# DriverAndProtection.net
KiCad netlist of a schematic drawn in Altium Designer
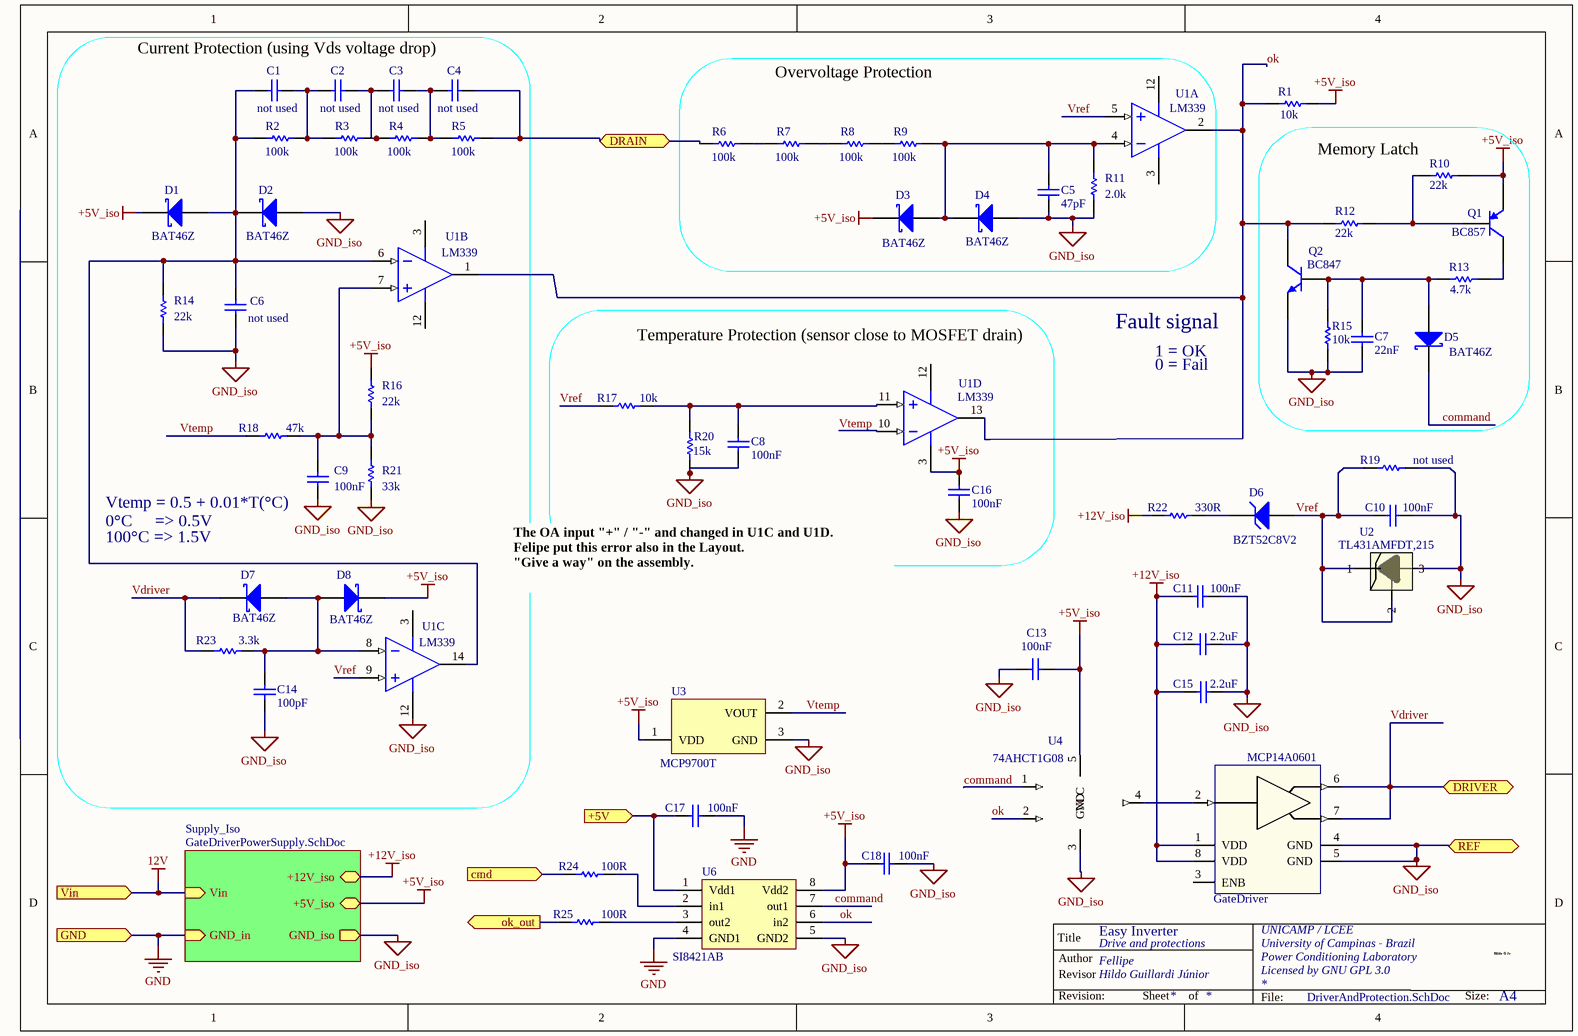
[diagram p0: DriverAndProtection.SchDoc]

(export (version "E")
  (design (tool "Eeschema 10.0.6"))
  (components
    (comp (ref "C1")
      (value "not used")
      (footprint "0805_W")
      (description "Capacitor")
      (fields (field (name "PUBLISHER") "Altium Limited"))
      (libsource (lib "Inversor_LCEE") (part "Cap_0805"))
    )
    (comp (ref "C2")
      (value "not used")
      (footprint "0805_W")
      (description "Capacitor")
      (fields (field (name "PUBLISHER") "Altium Limited"))
      (libsource (lib "Inversor_LCEE") (part "Cap_0805"))
    )
    (comp (ref "C3")
      (value "not used")
      (footprint "0805_W")
      (description "Capacitor")
      (fields (field (name "PUBLISHER") "Altium Limited"))
      (libsource (lib "Inversor_LCEE") (part "Cap_0805"))
    )
    (comp (ref "C4")
      (value "not used")
      (footprint "0805_W")
      (description "Capacitor")
      (fields (field (name "PUBLISHER") "Altium Limited"))
      (libsource (lib "Inversor_LCEE") (part "Cap_0805"))
    )
    (comp (ref "C5")
      (value "47pF")
      (footprint "0805_W")
      (description "Capacitor")
      (libsource (lib "Inversor_LCEE") (part "Cap_0805"))
    )
    (comp (ref "C6")
      (value "not used")
      (footprint "0805_W")
      (description "Capacitor")
      (libsource (lib "Inversor_LCEE") (part "Cap_0805"))
    )
    (comp (ref "C7")
      (value "22nF")
      (footprint "0805_W")
      (description "Capacitor")
      (libsource (lib "Inversor_LCEE") (part "Cap_0805"))
    )
    (comp (ref "C8")
      (value "100nF")
      (footprint "0805_W")
      (description "Capacitor")
      (libsource (lib "Inversor_LCEE") (part "Cap_0805"))
    )
    (comp (ref "C9")
      (value "100nF")
      (footprint "0805_W")
      (description "Capacitor")
      (libsource (lib "Inversor_LCEE") (part "Cap_0805"))
    )
    (comp (ref "C10")
      (value "100nF")
      (footprint "0805_W")
      (description "Capacitor")
      (libsource (lib "Inversor_LCEE") (part "Cap_0805"))
    )
    (comp (ref "C11")
      (value "100nF")
      (footprint "0805_W")
      (description "Capacitor")
      (libsource (lib "Inversor_LCEE") (part "Cap_0805"))
    )
    (comp (ref "C12")
      (value "2.2uF")
      (footprint "0805_W")
      (description "Capacitor nao polarizado")
      (libsource (lib "Sch_LCEE") (part "Capacitor_nao_polarizado"))
    )
    (comp (ref "C13")
      (value "100nF")
      (footprint "0805_W")
      (description "Capacitor")
      (libsource (lib "Inversor_LCEE") (part "Cap_0805"))
    )
    (comp (ref "C14")
      (value "100pF")
      (footprint "0805_W")
      (description "Capacitor")
      (libsource (lib "Inversor_LCEE") (part "Cap_0805"))
    )
    (comp (ref "C15")
      (value "2.2uF")
      (footprint "0805_W")
      (description "Capacitor nao polarizado")
      (libsource (lib "Sch_LCEE") (part "Capacitor_nao_polarizado"))
    )
    (comp (ref "C16")
      (value "100nF")
      (footprint "0805_W")
      (description "Capacitor")
      (libsource (lib "Inversor_LCEE") (part "Cap_0805"))
    )
    (comp (ref "C17")
      (value "100nF")
      (footprint "0805_W")
      (description "Capacitor")
      (libsource (lib "Inversor_LCEE") (part "Cap_0805"))
    )
    (comp (ref "C18")
      (value "100nF")
      (footprint "0805_W")
      (description "Capacitor")
      (libsource (lib "Inversor_LCEE") (part "Cap_0805"))
    )
    (comp (ref "D1")
      (value "BAT46Z")
      (footprint "pcb_lcee:SOD-123")
      (description "Schottky Diode")
      (libsource (lib "Miscellaneous Devices") (part "D Schottky"))
    )
    (comp (ref "D2")
      (value "BAT46Z")
      (footprint "pcb_lcee:SOD-123")
      (description "Schottky Diode")
      (libsource (lib "Miscellaneous Devices") (part "D Schottky"))
    )
    (comp (ref "D3")
      (value "BAT46Z")
      (footprint "pcb_lcee:SOD-123")
      (description "Schottky Diode")
      (libsource (lib "Miscellaneous Devices") (part "D Schottky"))
    )
    (comp (ref "D4")
      (value "BAT46Z")
      (footprint "pcb_lcee:SOD-123")
      (description "Schottky Diode")
      (libsource (lib "Miscellaneous Devices") (part "D Schottky"))
    )
    (comp (ref "D5")
      (value "BAT46Z")
      (footprint "SOD-123")
      (description "Diodo Schottky")
      (libsource (lib "Sch_LCEE") (part "Schottky"))
    )
    (comp (ref "D6")
      (value "BZT52C8V2")
      (footprint "SOD-123")
      (description "Zener Diode")
      (libsource (lib "Miscellaneous Devices") (part "D Zener"))
    )
    (comp (ref "D7")
      (value "BAT46Z")
      (footprint "pcb_lcee:SOD-123")
      (description "Schottky Diode")
      (libsource (lib "Miscellaneous Devices") (part "D Schottky"))
    )
    (comp (ref "D8")
      (value "BAT46Z")
      (footprint "pcb_lcee:SOD-123")
      (description "Schottky Diode")
      (libsource (lib "Miscellaneous Devices") (part "D Schottky"))
    )
    (comp (ref "GateDriver")
      (value "MCP14A0601")
      (footprint "SOIC-8N")
      (libsource (lib "Inverter_LCEE") (part "GateDriver"))
    )
    (comp (ref "Q1")
      (value "BC857")
      (footprint "SOT-23-TT3_N")
      (description "PNP General-purpose Transistor")
      (libsource (lib "Philips Discrete BJT - Low Power") (part "BC857"))
    )
    (comp (ref "Q2")
      (value "BC847")
      (footprint "SOT-23-TT3_N")
      (description "NPN General-purpose Transistor")
      (libsource (lib "Philips Discrete BJT - Low Power") (part "BC847"))
    )
    (comp (ref "R1")
      (value "10k")
      (footprint "0805_W")
      (description "Resistor")
      (libsource (lib "Inversor_LCEE") (part "Res_0805"))
    )
    (comp (ref "R2")
      (value "100k")
      (footprint "0805_W")
      (description "Resistor")
      (libsource (lib "Inversor_LCEE") (part "Res_0805"))
    )
    (comp (ref "R3")
      (value "100k")
      (footprint "0805_W")
      (description "Resistor")
      (libsource (lib "Inversor_LCEE") (part "Res_0805"))
    )
    (comp (ref "R4")
      (value "100k")
      (footprint "0805_W")
      (description "Resistor")
      (libsource (lib "Inversor_LCEE") (part "Res_0805"))
    )
    (comp (ref "R5")
      (value "100k")
      (footprint "0805_W")
      (description "Resistor")
      (libsource (lib "Inversor_LCEE") (part "Res_0805"))
    )
    (comp (ref "R6")
      (value "100k")
      (footprint "0805_W")
      (description "Resistor")
      (libsource (lib "Inversor_LCEE") (part "Res_0805"))
    )
    (comp (ref "R7")
      (value "100k")
      (footprint "0805_W")
      (description "Resistor")
      (libsource (lib "Inversor_LCEE") (part "Res_0805"))
    )
    (comp (ref "R8")
      (value "100k")
      (footprint "0805_W")
      (description "Resistor")
      (libsource (lib "Inversor_LCEE") (part "Res_0805"))
    )
    (comp (ref "R9")
      (value "100k")
      (footprint "0805_W")
      (description "Resistor")
      (libsource (lib "Inversor_LCEE") (part "Res_0805"))
    )
    (comp (ref "R10")
      (value "22k")
      (footprint "0805_W")
      (description "Resistor- Not Used")
      (libsource (lib "Inversor_LCEE") (part "Res_0805"))
    )
    (comp (ref "R11")
      (value "2.0k")
      (footprint "0805_W")
      (description "Resistor")
      (libsource (lib "Inversor_LCEE") (part "Res_0805"))
    )
    (comp (ref "R12")
      (value "22k")
      (footprint "0805_W")
      (description "Resistor")
      (libsource (lib "Inversor_LCEE") (part "Res_0805"))
    )
    (comp (ref "R13")
      (value "4.7k")
      (footprint "0805_W")
      (description "Resistor")
      (libsource (lib "Inversor_LCEE") (part "Res_0805"))
    )
    (comp (ref "R14")
      (value "22k")
      (footprint "0805_W")
      (description "Resistor")
      (libsource (lib "Inversor_LCEE") (part "Res_0805"))
    )
    (comp (ref "R15")
      (value "10k")
      (footprint "0805_W")
      (description "Resistor- Not Used")
      (libsource (lib "Inversor_LCEE") (part "Res_0805"))
    )
    (comp (ref "R16")
      (value "22k")
      (footprint "0805_W")
      (description "Resistor")
      (libsource (lib "Inversor_LCEE") (part "Res_0805"))
    )
    (comp (ref "R17")
      (value "10k")
      (footprint "0805_W")
      (description "Resistor")
      (libsource (lib "Inversor_LCEE") (part "Res_0805"))
    )
    (comp (ref "R18")
      (value "47k")
      (footprint "0805_W")
      (description "Resistor")
      (libsource (lib "Inversor_LCEE") (part "Res_0805"))
    )
    (comp (ref "R19")
      (value "not used")
      (footprint "0805_W")
      (description "Resistor- Not Used")
      (libsource (lib "Inversor_LCEE") (part "Res_0805"))
    )
    (comp (ref "R20")
      (value "15k")
      (footprint "0805_W")
      (description "Resistor")
      (libsource (lib "Inversor_LCEE") (part "Res_0805"))
    )
    (comp (ref "R21")
      (value "33k")
      (footprint "0805_W")
      (description "Resistor")
      (libsource (lib "Inversor_LCEE") (part "Res_0805"))
    )
    (comp (ref "R22")
      (value "330R")
      (footprint "0805_W")
      (description "Resistor- Not Used")
      (libsource (lib "Inversor_LCEE") (part "Res_0805"))
    )
    (comp (ref "R23")
      (value "3.3k")
      (footprint "0805_W")
      (description "Resistor")
      (libsource (lib "Inversor_LCEE") (part "Res_0805"))
    )
    (comp (ref "R24")
      (value "100R")
      (footprint "0805_W")
      (description "Resistor")
      (libsource (lib "Inversor_LCEE") (part "Res_0805"))
    )
    (comp (ref "R25")
      (value "100R")
      (footprint "0805_W")
      (description "Resistor")
      (libsource (lib "Inversor_LCEE") (part "Res_0805"))
    )
    (comp (ref "U1")
      (value "LM339")
      (footprint "SOIC-14N")
      (description "Low-Power Quad Voltage Comparator")
      (libsource (lib "ST Analog Comparator") (part "LM339AD"))
    )
    (comp (ref "U2")
      (value "TL431AMFDT,215")
      (footprint "SOT-23-TT3_M")
      (libsource (lib "Inversor_LCEE") (part "TL431ACLP"))
    )
    (comp (ref "U3")
      (value "MCP9700T")
      (footprint "SOT-23_L")
      (description "Low-Power Linear Active Thermistor IC, 3-Pin SOT-23, Extended Temperature, Tape and Reel")
      (libsource (lib "Microchip Thermal Management") (part "MCP9700T-E/TT"))
    )
    (comp (ref "U4") (value "74AHCT1G08") (footprint "SOT353") (libsource (lib "Inverter_LCEE") (part "AND")))
    (comp (ref "U6")
      (value "SI8421AB")
      (footprint "SOIC-8N")
      (description "Two Channel, High Speed Digital Isolators")
      (libsource (lib "Inverter_LCEE") (part "Si8421"))
    )
  )
  (nets
    (net (code "1") (name "+5V_iso") (class "Default")
      (node (ref "C13") (pin "1") (pinfunction "1_1") (pintype "passive"))
      (node (ref "C16") (pin "1") (pinfunction "1_1") (pintype "passive"))
      (node (ref "C18") (pin "2") (pinfunction "2_2") (pintype "passive"))
      (node (ref "D1") (pin "2") (pinfunction "K_2") (pintype "passive"))
      (node (ref "D3") (pin "2") (pinfunction "K_2") (pintype "passive"))
      (node (ref "D8") (pin "2") (pinfunction "K_2") (pintype "passive"))
      (node (ref "Q1") (pin "2") (pinfunction "E_2") (pintype "passive"))
      (node (ref "R1") (pin "2") (pinfunction "2_2") (pintype "passive"))
      (node (ref "R10") (pin "1") (pinfunction "1_1") (pintype "passive"))
      (node (ref "R16") (pin "2") (pinfunction "2_2") (pintype "passive"))
      (node (ref "U1") (pin "3") (pinfunction "V+_3") (pintype "power_in"))
      (node (ref "U3") (pin "1") (pinfunction "VDD_1") (pintype "power_in"))
      (node (ref "U4") (pin "5") (pinfunction "VCC_5") (pintype "power_in"))
      (node (ref "U6") (pin "8") (pinfunction "Vdd2_8") (pintype "passive"))
    )
    (net (code "2") (name "+12V_iso") (class "Default")
      (node (ref "C11") (pin "2") (pinfunction "2_2") (pintype "passive"))
      (node (ref "C12") (pin "1") (pinfunction "1_1") (pintype "passive"))
      (node (ref "C15") (pin "1") (pinfunction "1_1") (pintype "passive"))
      (node (ref "GateDriver") (pin "1") (pinfunction "VDD_1") (pintype "passive"))
      (node (ref "GateDriver") (pin "8") (pinfunction "VDD_8") (pintype "passive"))
      (node (ref "R22") (pin "1") (pinfunction "1_1") (pintype "passive"))
    )
    (net (code "3") (name "/+5V") (class "Default")
      (node (ref "C17") (pin "2") (pinfunction "2_2") (pintype "passive"))
      (node (ref "U6") (pin "1") (pinfunction "Vdd1_1") (pintype "passive"))
    )
    (net (code "4") (name "/DRAIN") (class "Default")
      (node (ref "C4") (pin "1") (pinfunction "1_1") (pintype "passive"))
      (node (ref "R5") (pin "2") (pinfunction "2_2") (pintype "passive"))
      (node (ref "R6") (pin "2") (pinfunction "2_2") (pintype "passive"))
    )
    (net (code "5") (name "/Vdriver") (class "Default")
      (node (ref "D7") (pin "2") (pinfunction "K_2") (pintype "passive"))
      (node (ref "GateDriver") (pin "6") (pintype "output"))
      (node (ref "GateDriver") (pin "7") (pintype "output"))
      (node (ref "R23") (pin "2") (pinfunction "2_2") (pintype "passive"))
    )
    (net (code "6") (name "/Vref") (class "Default")
      (node (ref "C10") (pin "1") (pinfunction "1_1") (pintype "passive"))
      (node (ref "D6") (pin "1") (pinfunction "A_1") (pintype "passive"))
      (node (ref "R17") (pin "2") (pinfunction "2_2") (pintype "passive"))
      (node (ref "R19") (pin "1") (pinfunction "1_1") (pintype "passive"))
      (node (ref "U1") (pin "5") (pinfunction "IN+_5") (pintype "input"))
      (node (ref "U1") (pin "9") (pinfunction "IN+_9") (pintype "input"))
      (node (ref "U2") (pin "1") (pinfunction "1_1") (pintype "passive"))
      (node (ref "U2") (pin "2") (pinfunction "2_2") (pintype "passive"))
    )
    (net (code "7") (name "/Vtemp") (class "Default")
      (node (ref "R18") (pin "2") (pinfunction "2_2") (pintype "passive"))
      (node (ref "U3") (pin "2") (pinfunction "VOUT_2") (pintype "power_in"))
    )
    (net (code "8") (name "/cmd") (class "Default")
      (node (ref "R24") (pin "2") (pinfunction "2_2") (pintype "passive"))
    )
    (net (code "9") (name "/command") (class "Default")
      (node (ref "D5") (pin "2") (pinfunction "K_2") (pintype "passive"))
      (node (ref "U4") (pin "1") (pinfunction "OE*_1") (pintype "input"))
      (node (ref "U6") (pin "7") (pinfunction "out1_7") (pintype "passive"))
    )
    (net (code "10") (name "/ok") (class "Default")
      (node (ref "Q2") (pin "3") (pinfunction "C_3") (pintype "passive"))
      (node (ref "R1") (pin "1") (pinfunction "1_1") (pintype "passive"))
      (node (ref "R12") (pin "2") (pinfunction "2_2") (pintype "passive"))
      (node (ref "U1") (pin "1") (pinfunction "OUT_1") (pintype "open_collector"))
      (node (ref "U1") (pin "13") (pinfunction "OUT_13") (pintype "open_collector"))
      (node (ref "U1") (pin "2") (pinfunction "OUT_2") (pintype "open_collector"))
      (node (ref "U4") (pin "2") (pinfunction "IN_2") (pintype "input"))
      (node (ref "U6") (pin "6") (pinfunction "in2_6") (pintype "passive"))
    )
    (net (code "11") (name "/ok_out") (class "Default")
      (node (ref "R25") (pin "2") (pinfunction "2_2") (pintype "passive"))
    )
    (net (code "13") (name "GND") (class "Default")
      (node (ref "C17") (pin "1") (pinfunction "1_1") (pintype "passive"))
      (node (ref "U6") (pin "4") (pinfunction "GND1_4") (pintype "passive"))
    )
    (net (code "14") (name "GND_iso") (class "Default")
      (node (ref "C10") (pin "2") (pinfunction "2_2") (pintype "passive"))
      (node (ref "C11") (pin "1") (pinfunction "1_1") (pintype "passive"))
      (node (ref "C12") (pin "2") (pinfunction "2_2") (pintype "passive"))
      (node (ref "C13") (pin "2") (pinfunction "2_2") (pintype "passive"))
      (node (ref "C14") (pin "2") (pinfunction "2_2") (pintype "passive"))
      (node (ref "C15") (pin "2") (pinfunction "2_2") (pintype "passive"))
      (node (ref "C16") (pin "2") (pinfunction "2_2") (pintype "passive"))
      (node (ref "C18") (pin "1") (pinfunction "1_1") (pintype "passive"))
      (node (ref "C5") (pin "2") (pinfunction "2_2") (pintype "passive"))
      (node (ref "C6") (pin "2") (pinfunction "2_2") (pintype "passive"))
      (node (ref "C7") (pin "2") (pinfunction "2_2") (pintype "passive"))
      (node (ref "C8") (pin "2") (pinfunction "2_2") (pintype "passive"))
      (node (ref "C9") (pin "2") (pinfunction "2_2") (pintype "passive"))
      (node (ref "D2") (pin "1") (pinfunction "A_1") (pintype "passive"))
      (node (ref "D4") (pin "1") (pinfunction "A_1") (pintype "passive"))
      (node (ref "GateDriver") (pin "4") (pinfunction "GND_4") (pintype "passive"))
      (node (ref "GateDriver") (pin "5") (pinfunction "GND_5") (pintype "passive"))
      (node (ref "Q2") (pin "2") (pinfunction "E_2") (pintype "passive"))
      (node (ref "R11") (pin "1") (pinfunction "1_1") (pintype "passive"))
      (node (ref "R14") (pin "1") (pinfunction "1_1") (pintype "passive"))
      (node (ref "R15") (pin "2") (pinfunction "2_2") (pintype "passive"))
      (node (ref "R19") (pin "2") (pinfunction "2_2") (pintype "passive"))
      (node (ref "R20") (pin "2") (pinfunction "2_2") (pintype "passive"))
      (node (ref "R21") (pin "2") (pinfunction "2_2") (pintype "passive"))
      (node (ref "U1") (pin "12") (pinfunction "V-_12") (pintype "power_in"))
      (node (ref "U2") (pin "3") (pinfunction "3_3") (pintype "passive"))
      (node (ref "U3") (pin "3") (pinfunction "GND_3") (pintype "power_in"))
      (node (ref "U4") (pin "3") (pinfunction "GND_3") (pintype "power_in"))
      (node (ref "U6") (pin "5") (pinfunction "GND2_5") (pintype "passive"))
    )
    (net (code "15") (name "Net-(C1-Pad1)") (class "Default")
      (node (ref "C1") (pin "1") (pinfunction "1_1") (pintype "passive"))
      (node (ref "C2") (pin "2") (pinfunction "2_2") (pintype "passive"))
      (node (ref "R2") (pin "2") (pinfunction "2_2") (pintype "passive"))
      (node (ref "R3") (pin "2") (pinfunction "2_2") (pintype "passive"))
    )
    (net (code "16") (name "Net-(C2-Pad1)") (class "Default")
      (node (ref "C2") (pin "1") (pinfunction "1_1") (pintype "passive"))
      (node (ref "C3") (pin "2") (pinfunction "2_2") (pintype "passive"))
      (node (ref "R3") (pin "1") (pinfunction "1_1") (pintype "passive"))
      (node (ref "R4") (pin "2") (pinfunction "2_2") (pintype "passive"))
    )
    (net (code "17") (name "Net-(C3-Pad1)") (class "Default")
      (node (ref "C3") (pin "1") (pinfunction "1_1") (pintype "passive"))
      (node (ref "C4") (pin "2") (pinfunction "2_2") (pintype "passive"))
      (node (ref "R4") (pin "1") (pinfunction "1_1") (pintype "passive"))
      (node (ref "R5") (pin "1") (pinfunction "1_1") (pintype "passive"))
    )
    (net (code "18") (name "Net-(D1-A)") (class "Default")
      (node (ref "C1") (pin "2") (pinfunction "2_2") (pintype "passive"))
      (node (ref "C6") (pin "1") (pinfunction "1_1") (pintype "passive"))
      (node (ref "D1") (pin "1") (pinfunction "A_1") (pintype "passive"))
      (node (ref "D2") (pin "2") (pinfunction "K_2") (pintype "passive"))
      (node (ref "R14") (pin "2") (pinfunction "2_2") (pintype "passive"))
      (node (ref "R2") (pin "1") (pinfunction "1_1") (pintype "passive"))
      (node (ref "U1") (pin "14") (pinfunction "OUT_14") (pintype "open_collector"))
      (node (ref "U1") (pin "6") (pinfunction "IN-_6") (pintype "input"))
    )
    (net (code "19") (name "Net-(D3-A)") (class "Default")
      (node (ref "C5") (pin "1") (pinfunction "1_1") (pintype "passive"))
      (node (ref "D3") (pin "1") (pinfunction "A_1") (pintype "passive"))
      (node (ref "D4") (pin "2") (pinfunction "K_2") (pintype "passive"))
      (node (ref "R11") (pin "2") (pinfunction "2_2") (pintype "passive"))
      (node (ref "R9") (pin "1") (pinfunction "1_1") (pintype "passive"))
      (node (ref "U1") (pin "4") (pinfunction "IN-_4") (pintype "input"))
    )
    (net (code "20") (name "Net-(D5-A)") (class "Default")
      (node (ref "C7") (pin "1") (pinfunction "1_1") (pintype "passive"))
      (node (ref "D5") (pin "1") (pinfunction "A_1") (pintype "passive"))
      (node (ref "Q2") (pin "1") (pinfunction "B_1") (pintype "passive"))
      (node (ref "R13") (pin "2") (pinfunction "2_2") (pintype "passive"))
      (node (ref "R15") (pin "1") (pinfunction "1_1") (pintype "passive"))
    )
    (net (code "21") (name "Net-(D6-K)") (class "Default")
      (node (ref "D6") (pin "2") (pinfunction "K_2") (pintype "passive"))
      (node (ref "R22") (pin "2") (pinfunction "2_2") (pintype "passive"))
    )
    (net (code "22") (name "Net-(D7-A)") (class "Default")
      (node (ref "C14") (pin "1") (pinfunction "1_1") (pintype "passive"))
      (node (ref "D7") (pin "1") (pinfunction "A_1") (pintype "passive"))
      (node (ref "D8") (pin "1") (pinfunction "A_1") (pintype "passive"))
      (node (ref "R23") (pin "1") (pinfunction "1_1") (pintype "passive"))
      (node (ref "U1") (pin "8") (pinfunction "IN-_8") (pintype "input"))
    )
    (net (code "23") (name "Net-(Q1-B)") (class "Default")
      (node (ref "Q1") (pin "1") (pinfunction "B_1") (pintype "passive"))
      (node (ref "R10") (pin "2") (pinfunction "2_2") (pintype "passive"))
      (node (ref "R12") (pin "1") (pinfunction "1_1") (pintype "passive"))
    )
    (net (code "24") (name "Net-(Q1-C)") (class "Default")
      (node (ref "Q1") (pin "3") (pinfunction "C_3") (pintype "passive"))
      (node (ref "R13") (pin "1") (pinfunction "1_1") (pintype "passive"))
    )
    (net (code "25") (name "Net-(R6-Pad1)") (class "Default")
      (node (ref "R6") (pin "1") (pinfunction "1_1") (pintype "passive"))
      (node (ref "R7") (pin "2") (pinfunction "2_2") (pintype "passive"))
    )
    (net (code "26") (name "Net-(R7-Pad1)") (class "Default")
      (node (ref "R7") (pin "1") (pinfunction "1_1") (pintype "passive"))
      (node (ref "R8") (pin "2") (pinfunction "2_2") (pintype "passive"))
    )
    (net (code "27") (name "Net-(R8-Pad1)") (class "Default")
      (node (ref "R8") (pin "1") (pinfunction "1_1") (pintype "passive"))
      (node (ref "R9") (pin "2") (pinfunction "2_2") (pintype "passive"))
    )
    (net (code "28") (name "Net-(U1B-IN+)") (class "Default")
      (node (ref "C9") (pin "1") (pinfunction "1_1") (pintype "passive"))
      (node (ref "R16") (pin "1") (pinfunction "1_1") (pintype "passive"))
      (node (ref "R18") (pin "1") (pinfunction "1_1") (pintype "passive"))
      (node (ref "R21") (pin "1") (pinfunction "1_1") (pintype "passive"))
      (node (ref "U1") (pin "7") (pinfunction "IN+_7") (pintype "input"))
    )
    (net (code "29") (name "Net-(U1D-IN+)") (class "Default")
      (node (ref "C8") (pin "1") (pinfunction "1_1") (pintype "passive"))
      (node (ref "R17") (pin "1") (pinfunction "1_1") (pintype "passive"))
      (node (ref "R20") (pin "1") (pinfunction "1_1") (pintype "passive"))
      (node (ref "U1") (pin "11") (pinfunction "IN+_11") (pintype "input"))
    )
    (net (code "30") (name "Net-(U4-OUT)") (class "Default")
      (node (ref "GateDriver") (pin "2") (pintype "input"))
      (node (ref "U4") (pin "4") (pinfunction "OUT_4") (pintype "output"))
    )
    (net (code "31") (name "Net-(U6-in1)") (class "Default")
      (node (ref "R24") (pin "1") (pinfunction "1_1") (pintype "passive"))
      (node (ref "U6") (pin "2") (pinfunction "in1_2") (pintype "passive"))
    )
    (net (code "32") (name "Net-(U6-out2)") (class "Default")
      (node (ref "R25") (pin "1") (pinfunction "1_1") (pintype "passive"))
      (node (ref "U6") (pin "3") (pinfunction "out2_3") (pintype "passive"))
    )
    (net (code "33") (name "unconnected-(GateDriver-ENB-Pad3)") (class "Default")
      (node (ref "GateDriver") (pin "3") (pinfunction "ENB_3") (pintype "passive"))
    )
    (net (code "34") (name "unconnected-(U1A-V+-Pad3)") (class "Default")
      (node (ref "U1") (pin "3") (pinfunction "V+_3") (pintype "power_in"))
    )
    (net (code "35") (name "unconnected-(U1A-V--Pad12)") (class "Default")
      (node (ref "U1") (pin "12") (pinfunction "V-_12") (pintype "power_in"))
    )
    (net (code "36") (name "unconnected-(U1B-V+-Pad3)") (class "Default")
      (node (ref "U1") (pin "3") (pinfunction "V+_3") (pintype "power_in"))
    )
    (net (code "37") (name "unconnected-(U1B-V--Pad12)") (class "Default")
      (node (ref "U1") (pin "12") (pinfunction "V-_12") (pintype "power_in"))
    )
    (net (code "38") (name "unconnected-(U1C-V+-Pad3)") (class "Default")
      (node (ref "U1") (pin "3") (pinfunction "V+_3") (pintype "power_in"))
    )
    (net (code "39") (name "unconnected-(U1D-IN--Pad10)") (class "Default")
      (node (ref "U1") (pin "10") (pinfunction "IN-_10") (pintype "input"))
    )
    (net (code "40") (name "unconnected-(U1D-V--Pad12)") (class "Default")
      (node (ref "U1") (pin "12") (pinfunction "V-_12") (pintype "power_in"))
    )
  )
)
